# sensor.net
KiCad netlist of a schematic drawn in EAGLE
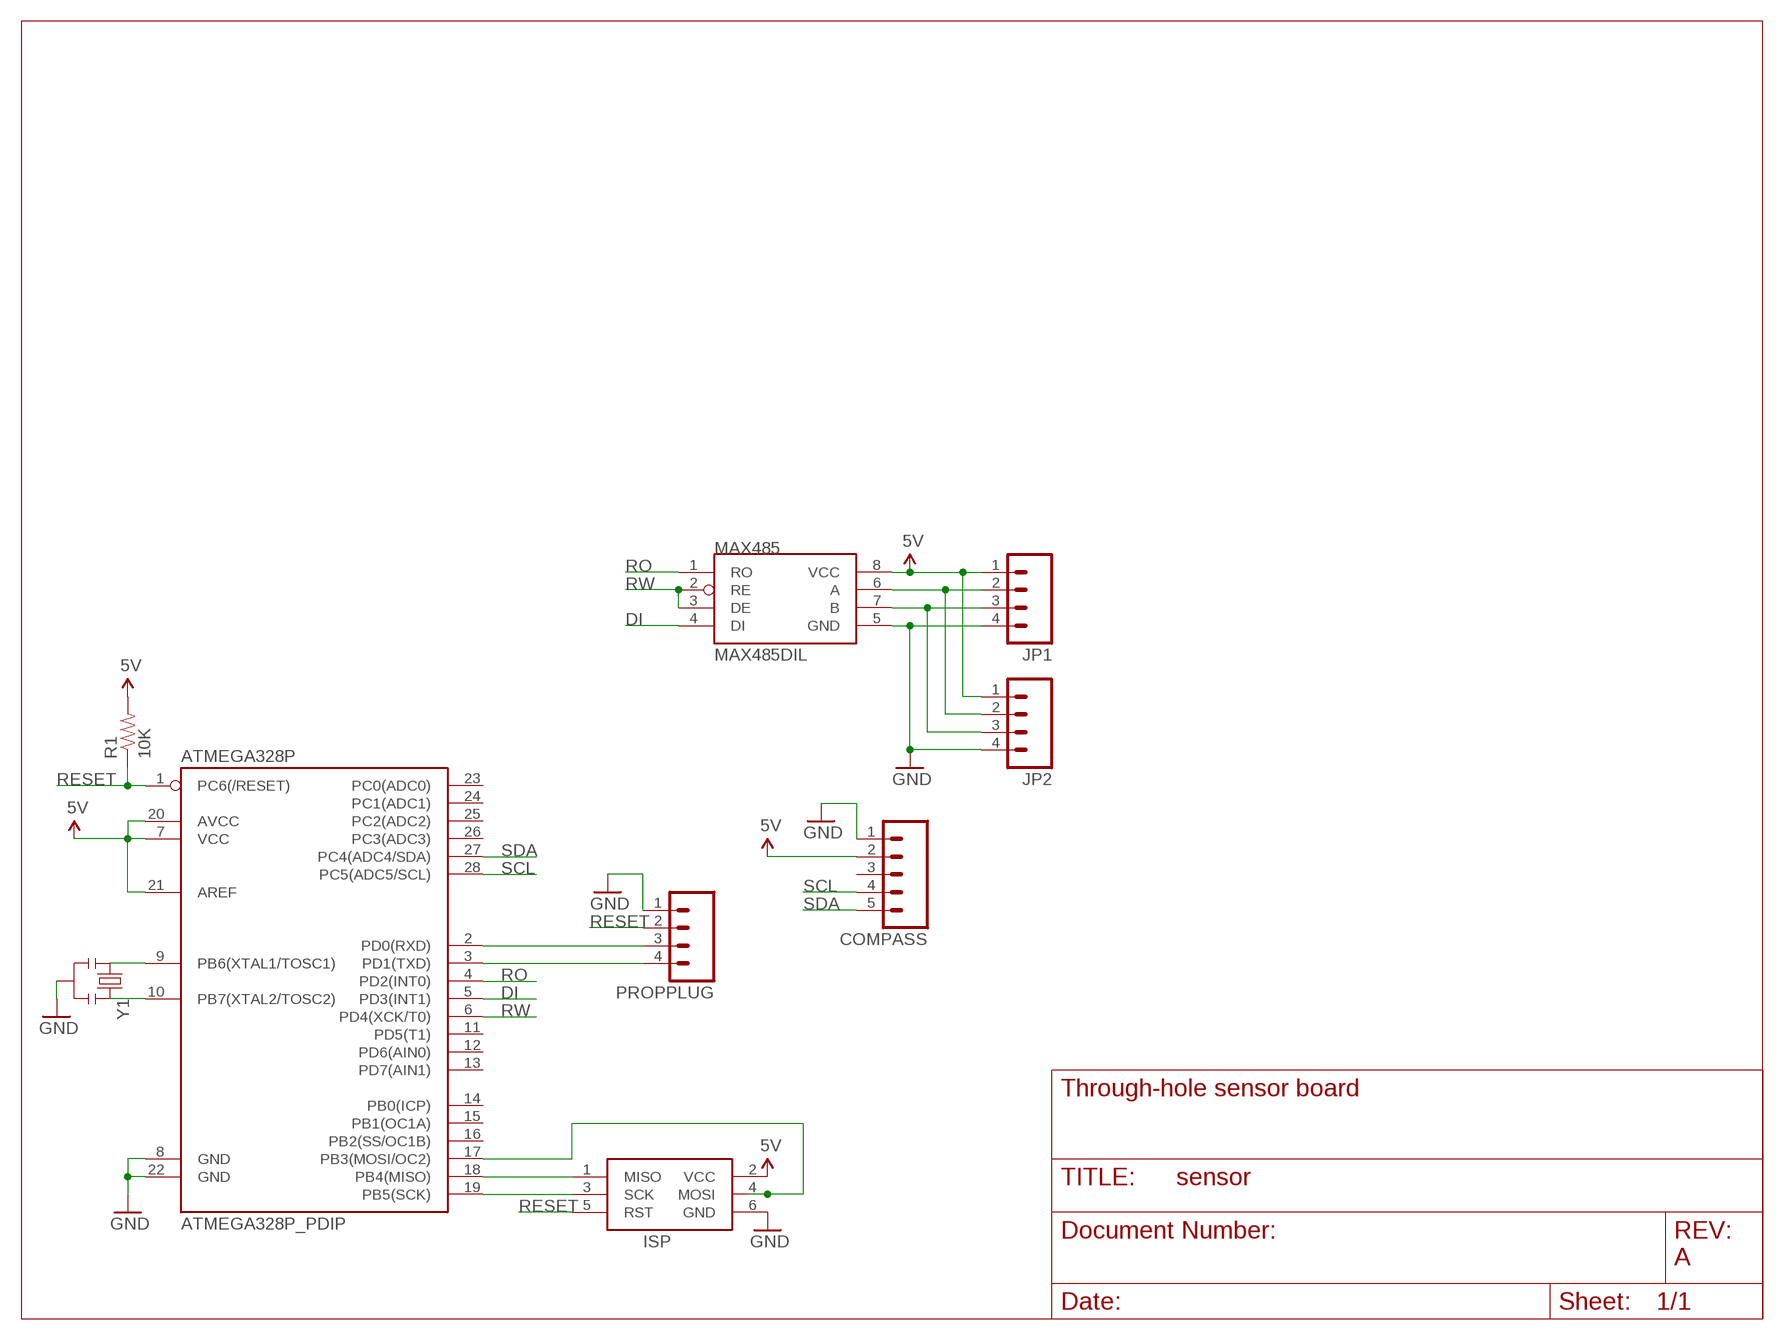
[diagram p0: schematic, sheet 1]

(export (version "E")
  (design (tool "Eeschema 10.0.6"))
  (components
    (comp (ref "ATMEGA328P")
      (value "ATMEGA328P_PDIP")
      (footprint "eagle-import:DIL28-3")
      (libsource (lib "eagle-import") (part "ATMEGA328P_PDIP"))
    )
    (comp (ref "COMPASS")
      (value "M05PTH")
      (footprint "eagle-import:1X05")
      (libsource (lib "eagle-import") (part "M05PTH"))
    )
    (comp (ref "ISP")
      (value "AVRISP-6")
      (footprint "eagle-import:AVRISP")
      (libsource (lib "eagle-import") (part "AVRISP-6"))
    )
    (comp (ref "JP1")
      (value "M04PTH")
      (footprint "eagle-import:1X04")
      (libsource (lib "eagle-import") (part "M04PTH"))
    )
    (comp (ref "JP2")
      (value "M04PTH")
      (footprint "eagle-import:1X04")
      (libsource (lib "eagle-import") (part "M04PTH"))
    )
    (comp (ref "MAX485")
      (value "MAX485DIL")
      (footprint "eagle-import:DIL08")
      (libsource (lib "eagle-import") (part "MAX485DIL"))
    )
    (comp (ref "PROPPLUG")
      (value "M04PTH")
      (footprint "eagle-import:1X04")
      (libsource (lib "eagle-import") (part "M04PTH"))
    )
    (comp (ref "R1")
      (value "10K")
      (footprint "eagle-import:AXIAL-0.4")
      (libsource (lib "eagle-import") (part "RESISTORPTH-1/4W"))
    )
    (comp (ref "Y1")
      (value "RESONATORPTH")
      (footprint "eagle-import:RESONATOR-PTH")
      (libsource (lib "eagle-import") (part "RESONATORPTH"))
    )
  )
  (nets
    (net (code "1") (name "/DI") (class "Default")
      (node (ref "ATMEGA328P") (pin "5") (pinfunction "PD3(INT1)_5") (pintype "bidirectional"))
      (node (ref "MAX485") (pin "4") (pinfunction "DI_4") (pintype "bidirectional"))
    )
    (net (code "2") (name "/RESET") (class "Default")
      (node (ref "ATMEGA328P") (pin "1") (pinfunction "PC6(/RESET)_1") (pintype "bidirectional"))
      (node (ref "ISP") (pin "5") (pinfunction "RST_5") (pintype "output"))
      (node (ref "PROPPLUG") (pin "2") (pinfunction "2_2") (pintype "passive"))
      (node (ref "R1") (pin "P$1") (pinfunction "1_P$1") (pintype "passive"))
    )
    (net (code "3") (name "/RO") (class "Default")
      (node (ref "ATMEGA328P") (pin "4") (pinfunction "PD2(INT0)_4") (pintype "bidirectional"))
      (node (ref "MAX485") (pin "1") (pinfunction "RO_1") (pintype "bidirectional"))
    )
    (net (code "4") (name "/RW") (class "Default")
      (node (ref "ATMEGA328P") (pin "6") (pinfunction "PD4(XCK/T0)_6") (pintype "bidirectional"))
      (node (ref "MAX485") (pin "2") (pinfunction "RE_2") (pintype "bidirectional"))
      (node (ref "MAX485") (pin "3") (pinfunction "DE_3") (pintype "bidirectional"))
    )
    (net (code "5") (name "/SCL") (class "Default")
      (node (ref "ATMEGA328P") (pin "28") (pinfunction "PC5(ADC5/SCL)_28") (pintype "bidirectional"))
      (node (ref "COMPASS") (pin "4") (pinfunction "4_4") (pintype "passive"))
    )
    (net (code "6") (name "/SDA") (class "Default")
      (node (ref "ATMEGA328P") (pin "27") (pinfunction "PC4(ADC4/SDA)_27") (pintype "bidirectional"))
      (node (ref "COMPASS") (pin "5") (pinfunction "5_5") (pintype "passive"))
    )
    (net (code "7") (name "5V") (class "Default")
      (node (ref "ATMEGA328P") (pin "20") (pinfunction "AVCC_20") (pintype "bidirectional"))
      (node (ref "ATMEGA328P") (pin "21") (pinfunction "AREF_21") (pintype "bidirectional"))
      (node (ref "ATMEGA328P") (pin "7") (pinfunction "VCC_7") (pintype "bidirectional"))
      (node (ref "COMPASS") (pin "2") (pinfunction "2_2") (pintype "passive"))
      (node (ref "ISP") (pin "2") (pinfunction "VCC_2") (pintype "power_in"))
      (node (ref "JP1") (pin "1") (pinfunction "1_1") (pintype "passive"))
      (node (ref "JP2") (pin "1") (pinfunction "1_1") (pintype "passive"))
      (node (ref "MAX485") (pin "8") (pinfunction "VCC_8") (pintype "bidirectional"))
      (node (ref "R1") (pin "P$2") (pinfunction "2_P$2") (pintype "passive"))
    )
    (net (code "8") (name "GND") (class "Default")
      (node (ref "ATMEGA328P") (pin "22") (pinfunction "GND_22") (pintype "bidirectional"))
      (node (ref "ATMEGA328P") (pin "8") (pinfunction "GND_8") (pintype "bidirectional"))
      (node (ref "COMPASS") (pin "1") (pinfunction "1_1") (pintype "passive"))
      (node (ref "ISP") (pin "6") (pinfunction "GND_6") (pintype "power_in"))
      (node (ref "JP1") (pin "4") (pinfunction "4_4") (pintype "passive"))
      (node (ref "JP2") (pin "4") (pinfunction "4_4") (pintype "passive"))
      (node (ref "MAX485") (pin "5") (pinfunction "GND_5") (pintype "bidirectional"))
      (node (ref "PROPPLUG") (pin "1") (pinfunction "1_1") (pintype "passive"))
      (node (ref "Y1") (pin "2") (pinfunction "2_2") (pintype "passive"))
    )
    (net (code "9") (name "Net-(ATMEGA328P-PB3(MOSI{slash}OC2))") (class "Default")
      (node (ref "ATMEGA328P") (pin "17") (pinfunction "PB3(MOSI/OC2)_17") (pintype "bidirectional"))
      (node (ref "ISP") (pin "4") (pinfunction "MOSI_4") (pintype "output"))
    )
    (net (code "10") (name "Net-(ATMEGA328P-PB4(MISO))") (class "Default")
      (node (ref "ATMEGA328P") (pin "18") (pinfunction "PB4(MISO)_18") (pintype "bidirectional"))
      (node (ref "ISP") (pin "1") (pinfunction "MISO_1") (pintype "input"))
    )
    (net (code "11") (name "Net-(ATMEGA328P-PB5(SCK))") (class "Default")
      (node (ref "ATMEGA328P") (pin "19") (pinfunction "PB5(SCK)_19") (pintype "bidirectional"))
      (node (ref "ISP") (pin "3") (pinfunction "SCK_3") (pintype "output"))
    )
    (net (code "12") (name "Net-(ATMEGA328P-PB6(XTAL1{slash}TOSC1))") (class "Default")
      (node (ref "ATMEGA328P") (pin "9") (pinfunction "PB6(XTAL1/TOSC1)_9") (pintype "bidirectional"))
      (node (ref "Y1") (pin "1") (pinfunction "1_1") (pintype "passive"))
    )
    (net (code "13") (name "Net-(ATMEGA328P-PB7(XTAL2{slash}TOSC2))") (class "Default")
      (node (ref "ATMEGA328P") (pin "10") (pinfunction "PB7(XTAL2/TOSC2)_10") (pintype "bidirectional"))
      (node (ref "Y1") (pin "3") (pinfunction "3_3") (pintype "passive"))
    )
    (net (code "14") (name "Net-(ATMEGA328P-PD0(RXD))") (class "Default")
      (node (ref "ATMEGA328P") (pin "2") (pinfunction "PD0(RXD)_2") (pintype "bidirectional"))
      (node (ref "PROPPLUG") (pin "3") (pinfunction "3_3") (pintype "passive"))
    )
    (net (code "15") (name "Net-(ATMEGA328P-PD1(TXD))") (class "Default")
      (node (ref "ATMEGA328P") (pin "3") (pinfunction "PD1(TXD)_3") (pintype "bidirectional"))
      (node (ref "PROPPLUG") (pin "4") (pinfunction "4_4") (pintype "passive"))
    )
    (net (code "16") (name "Net-(MAX485-A)") (class "Default")
      (node (ref "JP1") (pin "2") (pinfunction "2_2") (pintype "passive"))
      (node (ref "JP2") (pin "2") (pinfunction "2_2") (pintype "passive"))
      (node (ref "MAX485") (pin "6") (pinfunction "A_6") (pintype "bidirectional"))
    )
    (net (code "17") (name "Net-(MAX485-B)") (class "Default")
      (node (ref "JP1") (pin "3") (pinfunction "3_3") (pintype "passive"))
      (node (ref "JP2") (pin "3") (pinfunction "3_3") (pintype "passive"))
      (node (ref "MAX485") (pin "7") (pinfunction "B_7") (pintype "bidirectional"))
    )
    (net (code "18") (name "unconnected-(ATMEGA328P-PB0(ICP)-Pad14)") (class "Default")
      (node (ref "ATMEGA328P") (pin "14") (pinfunction "PB0(ICP)_14") (pintype "bidirectional"))
    )
    (net (code "19") (name "unconnected-(ATMEGA328P-PB1(OC1A)-Pad15)") (class "Default")
      (node (ref "ATMEGA328P") (pin "15") (pinfunction "PB1(OC1A)_15") (pintype "bidirectional"))
    )
    (net (code "20") (name "unconnected-(ATMEGA328P-PB2(SS{slash}OC1B)-Pad16)") (class "Default")
      (node (ref "ATMEGA328P") (pin "16") (pinfunction "PB2(SS/OC1B)_16") (pintype "bidirectional"))
    )
    (net (code "21") (name "unconnected-(ATMEGA328P-PC0(ADC0)-Pad23)") (class "Default")
      (node (ref "ATMEGA328P") (pin "23") (pinfunction "PC0(ADC0)_23") (pintype "bidirectional"))
    )
    (net (code "22") (name "unconnected-(ATMEGA328P-PC1(ADC1)-Pad24)") (class "Default")
      (node (ref "ATMEGA328P") (pin "24") (pinfunction "PC1(ADC1)_24") (pintype "bidirectional"))
    )
    (net (code "23") (name "unconnected-(ATMEGA328P-PC2(ADC2)-Pad25)") (class "Default")
      (node (ref "ATMEGA328P") (pin "25") (pinfunction "PC2(ADC2)_25") (pintype "bidirectional"))
    )
    (net (code "24") (name "unconnected-(ATMEGA328P-PC3(ADC3)-Pad26)") (class "Default")
      (node (ref "ATMEGA328P") (pin "26") (pinfunction "PC3(ADC3)_26") (pintype "bidirectional"))
    )
    (net (code "25") (name "unconnected-(ATMEGA328P-PD5(T1)-Pad11)") (class "Default")
      (node (ref "ATMEGA328P") (pin "11") (pinfunction "PD5(T1)_11") (pintype "bidirectional"))
    )
    (net (code "26") (name "unconnected-(ATMEGA328P-PD6(AIN0)-Pad12)") (class "Default")
      (node (ref "ATMEGA328P") (pin "12") (pinfunction "PD6(AIN0)_12") (pintype "bidirectional"))
    )
    (net (code "27") (name "unconnected-(ATMEGA328P-PD7(AIN1)-Pad13)") (class "Default")
      (node (ref "ATMEGA328P") (pin "13") (pinfunction "PD7(AIN1)_13") (pintype "bidirectional"))
    )
    (net (code "28") (name "unconnected-(COMPASS-Pad3)") (class "Default")
      (node (ref "COMPASS") (pin "3") (pinfunction "3_3") (pintype "passive"))
    )
  )
)
